# ethernet.net
KiCad netlist of a schematic drawn in Altium Designer
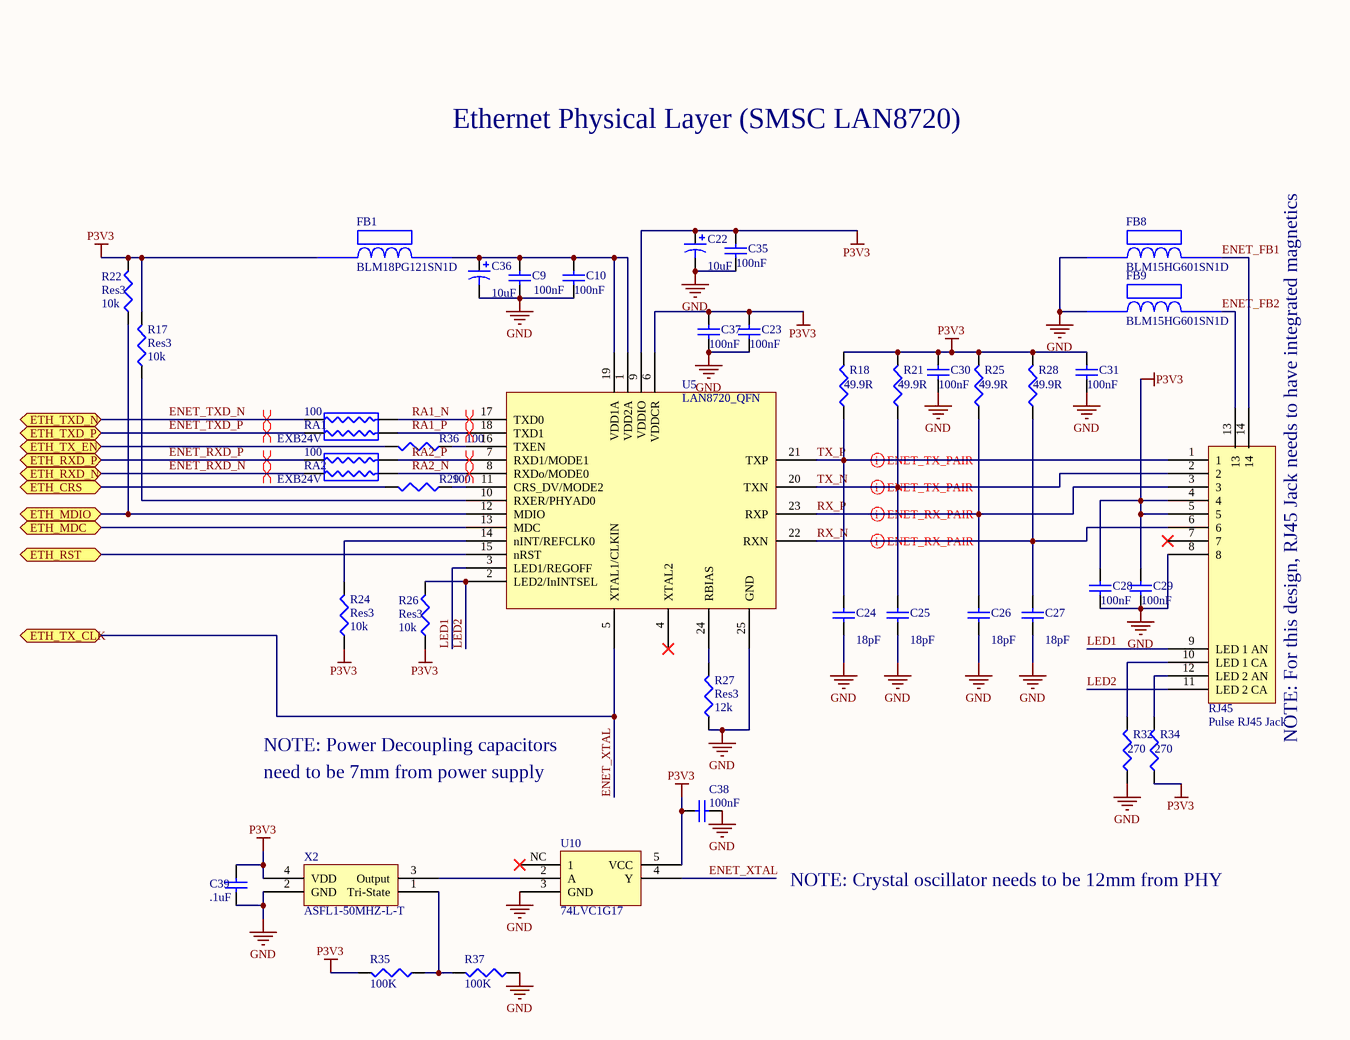
[diagram p0: ethernet.SchDoc]

(export (version "E")
  (design (tool "Eeschema 10.0.6"))
  (components
    (comp (ref "C9")
      (value "100nF")
      (footprint "1608[0603]")
      (description "Capacitor (Semiconductor SIM Model)")
      (fields (field (name "Comment") "Cap Semi") (field (name "PUBLISHER") "Altium Limited"))
      (libsource (lib "Miscellaneous Devices") (part "Cap Semi"))
    )
    (comp (ref "C10")
      (value "100nF")
      (footprint "1608[0603]")
      (description "Capacitor (Semiconductor SIM Model)")
      (fields (field (name "Comment") "Cap Semi") (field (name "PUBLISHER") "Altium Limited"))
      (libsource (lib "Miscellaneous Devices") (part "Cap Semi"))
    )
    (comp (ref "C22")
      (value "10uF")
      (footprint "CAPC1005X55N")
      (description "Polarized Capacitor (Surface Mount)")
      (fields (field (name "Comment") "Cap Pol3") (field (name "PUBLISHER") "Altium Limited"))
      (libsource (lib "Miscellaneous Devices") (part "Cap Pol3"))
    )
    (comp (ref "C23")
      (value "100nF")
      (footprint "1608[0603]")
      (description "Capacitor (Semiconductor SIM Model)")
      (fields (field (name "Comment") "Cap Semi") (field (name "PUBLISHER") "Altium Limited"))
      (libsource (lib "Miscellaneous Devices") (part "Cap Semi"))
    )
    (comp (ref "C24")
      (value "18pF")
      (footprint "1608[0603]")
      (description "Capacitor (Semiconductor SIM Model)")
      (fields (field (name "Comment") "Cap Semi") (field (name "PUBLISHER") "Altium Limited"))
      (libsource (lib "Miscellaneous Devices") (part "Cap Semi"))
    )
    (comp (ref "C25")
      (value "18pF")
      (footprint "1608[0603]")
      (description "Capacitor (Semiconductor SIM Model)")
      (fields (field (name "Comment") "Cap Semi") (field (name "PUBLISHER") "Altium Limited"))
      (libsource (lib "Miscellaneous Devices") (part "Cap Semi"))
    )
    (comp (ref "C26")
      (value "18pF")
      (footprint "1608[0603]")
      (description "Capacitor (Semiconductor SIM Model)")
      (fields (field (name "Comment") "Cap Semi") (field (name "PUBLISHER") "Altium Limited"))
      (libsource (lib "Miscellaneous Devices") (part "Cap Semi"))
    )
    (comp (ref "C27")
      (value "18pF")
      (footprint "1608[0603]")
      (description "Capacitor (Semiconductor SIM Model)")
      (fields (field (name "Comment") "Cap Semi") (field (name "PUBLISHER") "Altium Limited"))
      (libsource (lib "Miscellaneous Devices") (part "Cap Semi"))
    )
    (comp (ref "C28")
      (value "100nF")
      (footprint "1608[0603]")
      (description "Capacitor (Semiconductor SIM Model)")
      (fields (field (name "Comment") "Cap Semi") (field (name "PUBLISHER") "Altium Limited"))
      (libsource (lib "Miscellaneous Devices") (part "Cap Semi"))
    )
    (comp (ref "C29")
      (value "100nF")
      (footprint "1608[0603]")
      (description "Capacitor (Semiconductor SIM Model)")
      (fields (field (name "Comment") "Cap Semi") (field (name "PUBLISHER") "Altium Limited"))
      (libsource (lib "Miscellaneous Devices") (part "Cap Semi"))
    )
    (comp (ref "C30")
      (value "100nF")
      (footprint "1608[0603]")
      (description "Capacitor (Semiconductor SIM Model)")
      (fields (field (name "Comment") "Cap Semi") (field (name "PUBLISHER") "Altium Limited"))
      (libsource (lib "Miscellaneous Devices") (part "Cap Semi"))
    )
    (comp (ref "C31")
      (value "100nF")
      (footprint "1608[0603]")
      (description "Capacitor (Semiconductor SIM Model)")
      (fields (field (name "Comment") "Cap Semi") (field (name "PUBLISHER") "Altium Limited"))
      (libsource (lib "Miscellaneous Devices") (part "Cap Semi"))
    )
    (comp (ref "C35")
      (value "100nF")
      (footprint "1608[0603]")
      (description "Capacitor (Semiconductor SIM Model)")
      (fields (field (name "Comment") "Cap Semi") (field (name "PUBLISHER") "Altium Limited"))
      (libsource (lib "Miscellaneous Devices") (part "Cap Semi"))
    )
    (comp (ref "C36")
      (value "10uF")
      (footprint "1608[0603]")
      (description "Polarized Capacitor (Surface Mount)")
      (fields (field (name "Comment") "Cap Pol3") (field (name "PUBLISHER") "Altium Limited"))
      (libsource (lib "Miscellaneous Devices") (part "Cap Pol3"))
    )
    (comp (ref "C37")
      (value "100nF")
      (footprint "1608[0603]")
      (description "Capacitor (Semiconductor SIM Model)")
      (fields (field (name "Comment") "Cap Semi") (field (name "PUBLISHER") "Altium Limited"))
      (libsource (lib "Miscellaneous Devices") (part "Cap Semi"))
    )
    (comp (ref "C38")
      (value "100nF")
      (footprint "1608[0603]")
      (description "Capacitor (Semiconductor SIM Model)")
      (fields (field (name "Comment") "Cap Semi") (field (name "PUBLISHER") "Altium Limited"))
      (libsource (lib "Miscellaneous Devices") (part "Cap Semi"))
    )
    (comp (ref "C39")
      (value ".1uF")
      (footprint "1608[0603]")
      (description "Capacitor (Semiconductor SIM Model)")
      (fields (field (name "Comment") "Cap Semi") (field (name "PUBLISHER") "Altium Limited"))
      (libsource (lib "Miscellaneous Devices") (part "Cap Semi"))
    )
    (comp (ref "FB1")
      (value "BLM18PG121SN1D")
      (footprint "BLM18PG121SN1D")
      (libsource (lib "AHD Part Library") (part "BLM18PG121SN1D"))
    )
    (comp (ref "FB8")
      (value "BLM15HG601SN1D")
      (footprint "BLM18PG121SN1D")
      (libsource (lib "AHD Part Library") (part "BLM15HG601SN1D"))
    )
    (comp (ref "FB9")
      (value "BLM15HG601SN1D")
      (footprint "BLM18PG121SN1D")
      (libsource (lib "AHD Part Library") (part "BLM15HG601SN1D"))
    )
    (comp (ref "R17")
      (value "Res3")
      (footprint "J1-0603")
      (description "Resistor")
      (fields (field (name "ALTIUM_VALUE") "10k") (field (name "PUBLISHER") "Altium Limited"))
      (libsource (lib "Miscellaneous Devices") (part "Res3"))
    )
    (comp (ref "R18")
      (value "49.9R")
      (footprint "J1-0603")
      (description "Resistor")
      (fields (field (name "Comment") "Res3") (field (name "PUBLISHER") "Altium Limited"))
      (libsource (lib "Miscellaneous Devices") (part "Res3"))
    )
    (comp (ref "R21")
      (value "49.9R")
      (footprint "J1-0603")
      (description "Resistor")
      (fields (field (name "Comment") "Res3") (field (name "PUBLISHER") "Altium Limited"))
      (libsource (lib "Miscellaneous Devices") (part "Res3"))
    )
    (comp (ref "R22")
      (value "Res3")
      (footprint "J1-0603")
      (description "Resistor")
      (fields (field (name "ALTIUM_VALUE") "10k") (field (name "PUBLISHER") "Altium Limited"))
      (libsource (lib "Miscellaneous Devices") (part "Res3"))
    )
    (comp (ref "R24")
      (value "Res3")
      (footprint "J1-0603")
      (description "Resistor")
      (fields (field (name "ALTIUM_VALUE") "10k") (field (name "PUBLISHER") "Altium Limited"))
      (libsource (lib "Miscellaneous Devices") (part "Res3"))
    )
    (comp (ref "R25")
      (value "49.9R")
      (footprint "J1-0603")
      (description "Resistor")
      (fields (field (name "Comment") "Res3") (field (name "PUBLISHER") "Altium Limited"))
      (libsource (lib "Miscellaneous Devices") (part "Res3"))
    )
    (comp (ref "R26")
      (value "Res3")
      (footprint "J1-0603")
      (description "Resistor")
      (fields (field (name "ALTIUM_VALUE") "10k") (field (name "PUBLISHER") "Altium Limited"))
      (libsource (lib "Miscellaneous Devices") (part "Res3"))
    )
    (comp (ref "R27")
      (value "Res3")
      (footprint "J1-0603")
      (description "Resistor")
      (fields (field (name "ALTIUM_VALUE") "12k") (field (name "PUBLISHER") "Altium Limited"))
      (libsource (lib "Miscellaneous Devices") (part "Res3"))
    )
    (comp (ref "R28")
      (value "49.9R")
      (footprint "J1-0603")
      (description "Resistor")
      (fields (field (name "Comment") "Res3") (field (name "PUBLISHER") "Altium Limited"))
      (libsource (lib "Miscellaneous Devices") (part "Res3"))
    )
    (comp (ref "R29")
      (value "100")
      (footprint "J1-0603")
      (description "Resistor")
      (fields (field (name "Comment") "Res3") (field (name "PUBLISHER") "Altium Limited"))
      (libsource (lib "Miscellaneous Devices") (part "Res3"))
    )
    (comp (ref "R32")
      (value "270")
      (footprint "J1-0603")
      (description "Resistor")
      (fields (field (name "Comment") "Res3") (field (name "PUBLISHER") "Altium Limited"))
      (libsource (lib "Miscellaneous Devices") (part "Res3"))
    )
    (comp (ref "R34")
      (value "270")
      (footprint "J1-0603")
      (description "Resistor")
      (fields (field (name "Comment") "Res3") (field (name "PUBLISHER") "Altium Limited"))
      (libsource (lib "Miscellaneous Devices") (part "Res3"))
    )
    (comp (ref "R35")
      (value "100K")
      (footprint "J1-0603")
      (description "Resistor")
      (fields (field (name "Comment") "Res3") (field (name "PUBLISHER") "Altium Limited"))
      (libsource (lib "Miscellaneous Devices") (part "Res3"))
    )
    (comp (ref "R36")
      (value "100")
      (footprint "J1-0603")
      (description "Resistor")
      (fields (field (name "Comment") "Res3") (field (name "PUBLISHER") "Altium Limited"))
      (libsource (lib "Miscellaneous Devices") (part "Res3"))
    )
    (comp (ref "R37")
      (value "100K")
      (footprint "J1-0603")
      (description "Resistor")
      (fields (field (name "Comment") "Res3") (field (name "PUBLISHER") "Altium Limited"))
      (libsource (lib "Miscellaneous Devices") (part "Res3"))
    )
    (comp (ref "RA1")
      (value "EXB24V")
      (footprint "EXB24V - Res Array x2")
      (fields (field (name "ALTIUM_VALUE") "100"))
      (libsource (lib "AHD Part Library") (part "EXB24V - Res Array x2"))
    )
    (comp (ref "RA2")
      (value "EXB24V")
      (footprint "EXB24V - Res Array x2")
      (fields (field (name "ALTIUM_VALUE") "100"))
      (libsource (lib "AHD Part Library") (part "EXB24V - Res Array x2"))
    )
    (comp (ref "RJ45")
      (value "Pulse RJ45 Jack")
      (footprint "J0006D21BNL")
      (libsource (lib "AHD Part Library") (part "Pulse RJ45_ICM_LED_Jack"))
    )
    (comp (ref "U5")
      (value "LAN8720_QFN")
      (footprint "LAN8720_QFN")
      (libsource (lib "AHD Part Library") (part "LAN8720 QFN"))
    )
    (comp (ref "U10")
      (value "74LVC1G17")
      (footprint "74LVC1G17")
      (libsource (lib "AHD Part Library") (part "74LVC1G17"))
    )
    (comp (ref "X2")
      (value "ASFL1-50MHZ-L-T")
      (footprint "ASFL1-50MHZ-L-T")
      (libsource (lib "AHD Part Library") (part "ASFL1-50MHZ-L-T"))
    )
  )
  (nets
    (net (code "1") (name "/ENET_FB1") (class "Default")
      (node (ref "FB8") (pin "2") (pinfunction "2_2") (pintype "passive"))
      (node (ref "RJ45") (pin "14") (pinfunction "14_14") (pintype "passive"))
    )
    (net (code "2") (name "/ENET_FB2") (class "Default")
      (node (ref "FB9") (pin "2") (pinfunction "2_2") (pintype "passive"))
      (node (ref "RJ45") (pin "13") (pinfunction "13_13") (pintype "passive"))
    )
    (net (code "3") (name "/ENET_RXD_N") (class "Default")
      (node (ref "RA2") (pin "1") (pinfunction "1_1") (pintype "passive"))
    )
    (net (code "4") (name "/ENET_RXD_P") (class "Default")
      (node (ref "RA2") (pin "3") (pinfunction "3_3") (pintype "passive"))
    )
    (net (code "5") (name "/ENET_TXD_N") (class "Default")
      (node (ref "RA1") (pin "3") (pinfunction "3_3") (pintype "passive"))
    )
    (net (code "6") (name "/ENET_TXD_P") (class "Default")
      (node (ref "RA1") (pin "1") (pinfunction "1_1") (pintype "passive"))
    )
    (net (code "7") (name "/ENET_XTAL") (class "Default")
      (node (ref "U10") (pin "4") (pinfunction "Y_4") (pintype "passive"))
      (node (ref "U5") (pin "5") (pinfunction "XTAL1/CLKIN_5") (pintype "passive"))
    )
    (net (code "8") (name "/ETH_CRS") (class "Default")
      (node (ref "R29") (pin "2") (pinfunction "2_2") (pintype "passive"))
    )
    (net (code "9") (name "/ETH_MDC") (class "Default")
      (node (ref "U5") (pin "13") (pinfunction "MDC_13") (pintype "passive"))
    )
    (net (code "10") (name "/ETH_MDIO") (class "Default")
      (node (ref "R22") (pin "1") (pinfunction "1_1") (pintype "passive"))
      (node (ref "U5") (pin "12") (pinfunction "MDIO_12") (pintype "passive"))
    )
    (net (code "11") (name "/ETH_RST") (class "Default")
      (node (ref "U5") (pin "15") (pinfunction "nRST_15") (pintype "passive"))
    )
    (net (code "12") (name "/ETH_TX_EN") (class "Default")
      (node (ref "R36") (pin "2") (pinfunction "2_2") (pintype "passive"))
    )
    (net (code "13") (name "/LED1") (class "Default")
      (node (ref "RJ45") (pin "9") (pinfunction "LED_1_AN_9") (pintype "passive"))
      (node (ref "U5") (pin "3") (pinfunction "LED1/REGOFF_3") (pintype "passive"))
    )
    (net (code "14") (name "/LED2") (class "Default")
      (node (ref "R26") (pin "2") (pinfunction "2_2") (pintype "passive"))
      (node (ref "RJ45") (pin "11") (pinfunction "LED_2_CA_11") (pintype "passive"))
      (node (ref "U5") (pin "2") (pinfunction "LED2/InINTSEL_2") (pintype "passive"))
    )
    (net (code "15") (name "/RA1_N") (class "Default")
      (node (ref "RA1") (pin "4") (pinfunction "4_4") (pintype "passive"))
      (node (ref "U5") (pin "17") (pinfunction "TXD0_17") (pintype "passive"))
    )
    (net (code "16") (name "/RA1_P") (class "Default")
      (node (ref "RA1") (pin "2") (pinfunction "2_2") (pintype "passive"))
      (node (ref "U5") (pin "18") (pinfunction "TXD1_18") (pintype "passive"))
    )
    (net (code "17") (name "/RA2_N") (class "Default")
      (node (ref "RA2") (pin "2") (pinfunction "2_2") (pintype "passive"))
      (node (ref "U5") (pin "8") (pinfunction "RXDo/MODE0_8") (pintype "passive"))
    )
    (net (code "18") (name "/RA2_P") (class "Default")
      (node (ref "RA2") (pin "4") (pinfunction "4_4") (pintype "passive"))
      (node (ref "U5") (pin "7") (pinfunction "RXD1/MODE1_7") (pintype "passive"))
    )
    (net (code "19") (name "/RX_N") (class "Default")
      (node (ref "C27") (pin "2") (pinfunction "2_2") (pintype "passive"))
      (node (ref "R28") (pin "1") (pinfunction "1_1") (pintype "passive"))
      (node (ref "RJ45") (pin "6") (pinfunction "6_6") (pintype "passive"))
      (node (ref "U5") (pin "22") (pinfunction "RXN_22") (pintype "passive"))
    )
    (net (code "20") (name "/RX_P") (class "Default")
      (node (ref "C26") (pin "2") (pinfunction "2_2") (pintype "passive"))
      (node (ref "R25") (pin "1") (pinfunction "1_1") (pintype "passive"))
      (node (ref "RJ45") (pin "3") (pinfunction "3_3") (pintype "passive"))
      (node (ref "U5") (pin "23") (pinfunction "RXP_23") (pintype "passive"))
    )
    (net (code "21") (name "/TX_N") (class "Default")
      (node (ref "C25") (pin "2") (pinfunction "2_2") (pintype "passive"))
      (node (ref "R21") (pin "1") (pinfunction "1_1") (pintype "passive"))
      (node (ref "RJ45") (pin "2") (pinfunction "2_2") (pintype "passive"))
      (node (ref "U5") (pin "20") (pinfunction "TXN_20") (pintype "passive"))
    )
    (net (code "22") (name "/TX_P") (class "Default")
      (node (ref "C24") (pin "2") (pinfunction "2_2") (pintype "passive"))
      (node (ref "R18") (pin "1") (pinfunction "1_1") (pintype "passive"))
      (node (ref "RJ45") (pin "1") (pinfunction "1_1") (pintype "passive"))
      (node (ref "U5") (pin "21") (pinfunction "TXP_21") (pintype "passive"))
    )
    (net (code "23") (name "GND") (class "Default")
      (node (ref "C10") (pin "1") (pinfunction "1_1") (pintype "passive"))
      (node (ref "C22") (pin "2") (pinfunction "2_2") (pintype "passive"))
      (node (ref "C23") (pin "1") (pinfunction "1_1") (pintype "passive"))
      (node (ref "C24") (pin "1") (pinfunction "1_1") (pintype "passive"))
      (node (ref "C25") (pin "1") (pinfunction "1_1") (pintype "passive"))
      (node (ref "C26") (pin "1") (pinfunction "1_1") (pintype "passive"))
      (node (ref "C27") (pin "1") (pinfunction "1_1") (pintype "passive"))
      (node (ref "C28") (pin "1") (pinfunction "1_1") (pintype "passive"))
      (node (ref "C29") (pin "1") (pinfunction "1_1") (pintype "passive"))
      (node (ref "C30") (pin "1") (pinfunction "1_1") (pintype "passive"))
      (node (ref "C31") (pin "1") (pinfunction "1_1") (pintype "passive"))
      (node (ref "C35") (pin "1") (pinfunction "1_1") (pintype "passive"))
      (node (ref "C36") (pin "2") (pinfunction "2_2") (pintype "passive"))
      (node (ref "C37") (pin "1") (pinfunction "1_1") (pintype "passive"))
      (node (ref "C38") (pin "1") (pinfunction "1_1") (pintype "passive"))
      (node (ref "C39") (pin "1") (pinfunction "1_1") (pintype "passive"))
      (node (ref "C9") (pin "1") (pinfunction "1_1") (pintype "passive"))
      (node (ref "FB8") (pin "1") (pinfunction "1_1") (pintype "passive"))
      (node (ref "FB9") (pin "1") (pinfunction "1_1") (pintype "passive"))
      (node (ref "R27") (pin "1") (pinfunction "1_1") (pintype "passive"))
      (node (ref "R32") (pin "1") (pinfunction "1_1") (pintype "passive"))
      (node (ref "R37") (pin "1") (pinfunction "1_1") (pintype "passive"))
      (node (ref "RJ45") (pin "8") (pinfunction "8_8") (pintype "passive"))
      (node (ref "U10") (pin "3") (pinfunction "GND_3") (pintype "passive"))
      (node (ref "U5") (pin "25") (pinfunction "GND_25") (pintype "passive"))
      (node (ref "X2") (pin "2") (pinfunction "GND_2") (pintype "passive"))
    )
    (net (code "24") (name "Net-(RJ45-LED_1_CA)") (class "Default")
      (node (ref "R32") (pin "2") (pinfunction "2_2") (pintype "passive"))
      (node (ref "RJ45") (pin "10") (pinfunction "LED_1_CA_10") (pintype "passive"))
    )
    (net (code "25") (name "Net-(RJ45-LED_2_AN)") (class "Default")
      (node (ref "R34") (pin "2") (pinfunction "2_2") (pintype "passive"))
      (node (ref "RJ45") (pin "12") (pinfunction "LED_2_AN_12") (pintype "passive"))
    )
    (net (code "26") (name "Net-(U5-CRS_DV{slash}MODE2)") (class "Default")
      (node (ref "R29") (pin "1") (pinfunction "1_1") (pintype "passive"))
      (node (ref "U5") (pin "11") (pinfunction "CRS_DV/MODE2_11") (pintype "passive"))
    )
    (net (code "27") (name "Net-(U5-RBIAS)") (class "Default")
      (node (ref "R27") (pin "2") (pinfunction "2_2") (pintype "passive"))
      (node (ref "U5") (pin "24") (pinfunction "RBIAS_24") (pintype "passive"))
    )
    (net (code "28") (name "Net-(U5-RXER{slash}PHYAD0)") (class "Default")
      (node (ref "R17") (pin "1") (pinfunction "1_1") (pintype "passive"))
      (node (ref "U5") (pin "10") (pinfunction "RXER/PHYAD0_10") (pintype "passive"))
    )
    (net (code "29") (name "Net-(U5-TXEN)") (class "Default")
      (node (ref "R36") (pin "1") (pinfunction "1_1") (pintype "passive"))
      (node (ref "U5") (pin "16") (pinfunction "TXEN_16") (pintype "passive"))
    )
    (net (code "30") (name "Net-(U5-VDD1A)") (class "Default")
      (node (ref "C10") (pin "2") (pinfunction "2_2") (pintype "passive"))
      (node (ref "C36") (pin "1") (pinfunction "1_1") (pintype "passive"))
      (node (ref "C9") (pin "2") (pinfunction "2_2") (pintype "passive"))
      (node (ref "FB1") (pin "2") (pinfunction "2_2") (pintype "passive"))
      (node (ref "U5") (pin "1") (pinfunction "VDD2A_1") (pintype "passive"))
      (node (ref "U5") (pin "19") (pinfunction "VDD1A_19") (pintype "passive"))
    )
    (net (code "31") (name "Net-(U5-nINT{slash}REFCLK0)") (class "Default")
      (node (ref "R24") (pin "2") (pinfunction "2_2") (pintype "passive"))
      (node (ref "U5") (pin "14") (pinfunction "nINT/REFCLK0_14") (pintype "passive"))
    )
    (net (code "32") (name "Net-(U10-A)") (class "Default")
      (node (ref "U10") (pin "2") (pinfunction "A_2") (pintype "passive"))
      (node (ref "X2") (pin "3") (pinfunction "Output_3") (pintype "passive"))
    )
    (net (code "33") (name "Net-(X2-Tri-State)") (class "Default")
      (node (ref "R35") (pin "1") (pinfunction "1_1") (pintype "passive"))
      (node (ref "R37") (pin "2") (pinfunction "2_2") (pintype "passive"))
      (node (ref "X2") (pin "1") (pinfunction "Tri-State_1") (pintype "passive"))
    )
    (net (code "34") (name "P3V3") (class "Default")
      (node (ref "C22") (pin "1") (pinfunction "1_1") (pintype "passive"))
      (node (ref "C23") (pin "2") (pinfunction "2_2") (pintype "passive"))
      (node (ref "C28") (pin "2") (pinfunction "2_2") (pintype "passive"))
      (node (ref "C29") (pin "2") (pinfunction "2_2") (pintype "passive"))
      (node (ref "C30") (pin "2") (pinfunction "2_2") (pintype "passive"))
      (node (ref "C31") (pin "2") (pinfunction "2_2") (pintype "passive"))
      (node (ref "C35") (pin "2") (pinfunction "2_2") (pintype "passive"))
      (node (ref "C37") (pin "2") (pinfunction "2_2") (pintype "passive"))
      (node (ref "C38") (pin "2") (pinfunction "2_2") (pintype "passive"))
      (node (ref "C39") (pin "2") (pinfunction "2_2") (pintype "passive"))
      (node (ref "FB1") (pin "1") (pinfunction "1_1") (pintype "passive"))
      (node (ref "R17") (pin "2") (pinfunction "2_2") (pintype "passive"))
      (node (ref "R18") (pin "2") (pinfunction "2_2") (pintype "passive"))
      (node (ref "R21") (pin "2") (pinfunction "2_2") (pintype "passive"))
      (node (ref "R22") (pin "2") (pinfunction "2_2") (pintype "passive"))
      (node (ref "R24") (pin "1") (pinfunction "1_1") (pintype "passive"))
      (node (ref "R25") (pin "2") (pinfunction "2_2") (pintype "passive"))
      (node (ref "R26") (pin "1") (pinfunction "1_1") (pintype "passive"))
      (node (ref "R28") (pin "2") (pinfunction "2_2") (pintype "passive"))
      (node (ref "R34") (pin "1") (pinfunction "1_1") (pintype "passive"))
      (node (ref "R35") (pin "2") (pinfunction "2_2") (pintype "passive"))
      (node (ref "RJ45") (pin "4") (pinfunction "4_4") (pintype "passive"))
      (node (ref "RJ45") (pin "5") (pinfunction "5_5") (pintype "passive"))
      (node (ref "U10") (pin "5") (pinfunction "VCC_5") (pintype "passive"))
      (node (ref "U5") (pin "6") (pinfunction "VDDCR_6") (pintype "passive"))
      (node (ref "U5") (pin "9") (pinfunction "VDDIO_9") (pintype "passive"))
      (node (ref "X2") (pin "4") (pinfunction "VDD_4") (pintype "passive"))
    )
    (net (code "35") (name "unconnected-(RJ45-Pad7)") (class "Default")
      (node (ref "RJ45") (pin "7") (pinfunction "7_7") (pintype "passive+no_connect"))
    )
    (net (code "36") (name "unconnected-(U5-XTAL2-Pad4)") (class "Default")
      (node (ref "U5") (pin "4") (pinfunction "XTAL2_4") (pintype "passive+no_connect"))
    )
    (net (code "37") (name "unconnected-(U10-1-PadNC)") (class "Default")
      (node (ref "U10") (pin "NC") (pinfunction "1_NC") (pintype "passive+no_connect"))
    )
  )
)
